# gsm_based_message_display_on_lcd.net
KiCad netlist of a schematic drawn in EAGLE
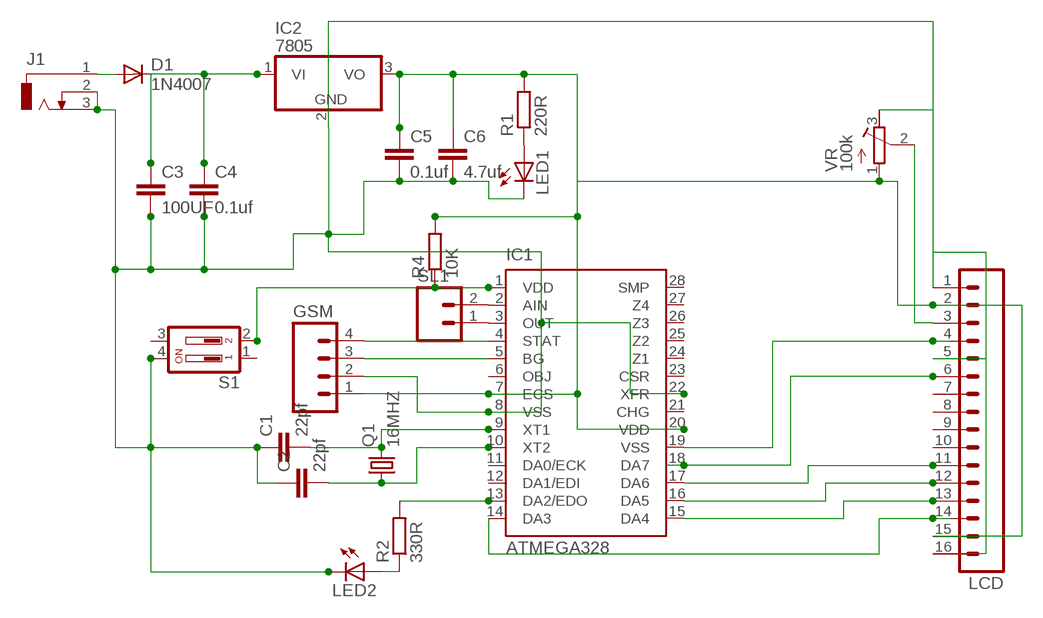
[diagram p0: schematic, sheet 1]

(export (version "E")
  (design (tool "Eeschema 10.0.6"))
  (components
    (comp (ref "C1")
      (value "22pf")
      (footprint "eagle-import:C2.5-2")
      (libsource (lib "eagle-import") (part "C2.5/2"))
    )
    (comp (ref "C2")
      (value "22pf")
      (footprint "eagle-import:C2.5-2")
      (libsource (lib "eagle-import") (part "C2.5/2"))
    )
    (comp (ref "C3")
      (value "100UF")
      (footprint "eagle-import:C2.5-2")
      (libsource (lib "eagle-import") (part "C2.5/2"))
    )
    (comp (ref "C4")
      (value "0.1uf")
      (footprint "eagle-import:C2.5-2")
      (libsource (lib "eagle-import") (part "C2.5/2"))
    )
    (comp (ref "C5")
      (value "0.1uf")
      (footprint "eagle-import:C2.5-2")
      (libsource (lib "eagle-import") (part "C2.5/2"))
    )
    (comp (ref "C6")
      (value "4.7uf")
      (footprint "eagle-import:C2.5-2")
      (libsource (lib "eagle-import") (part "C2.5/2"))
    )
    (comp (ref "D1")
      (value "1N4007")
      (footprint "eagle-import:DO41-10")
      (libsource (lib "eagle-import") (part "1N4004"))
    )
    (comp (ref "GSM")
      (value "M04")
      (footprint "eagle-import:04P")
      (libsource (lib "eagle-import") (part "M04"))
    )
    (comp (ref "IC1")
      (value "ATMEGA328")
      (footprint "eagle-import:DIL28-3")
      (libsource (lib "eagle-import") (part "QT9701BD"))
    )
    (comp (ref "IC2")
      (value "7805")
      (footprint "eagle-import:TO220V")
      (libsource (lib "eagle-import") (part "78TV6"))
    )
    (comp (ref "J1")
      (value "DCJ0303")
      (footprint "eagle-import:DCJ0303")
      (libsource (lib "eagle-import") (part "DCJ0303"))
    )
    (comp (ref "LCD")
      (value "M16")
      (footprint "eagle-import:16P")
      (libsource (lib "eagle-import") (part "M16"))
    )
    (comp (ref "LED1")
      (value "LED3MM")
      (footprint "eagle-import:LED3MM")
      (libsource (lib "eagle-import") (part "LED3MM"))
    )
    (comp (ref "LED2")
      (value "LED3MM")
      (footprint "eagle-import:LED3MM")
      (libsource (lib "eagle-import") (part "LED3MM"))
    )
    (comp (ref "Q1")
      (value "16MHZ")
      (footprint "eagle-import:HC49_S")
      (libsource (lib "eagle-import") (part "CRYSTALHC49S"))
    )
    (comp (ref "R1")
      (value "220R")
      (footprint "eagle-import:0207_10")
      (libsource (lib "eagle-import") (part "R-EU_0207/10"))
    )
    (comp (ref "R2")
      (value "330R")
      (footprint "eagle-import:0207_10")
      (libsource (lib "eagle-import") (part "R-EU_0207/10"))
    )
    (comp (ref "R4")
      (value "10K")
      (footprint "eagle-import:0207_10")
      (libsource (lib "eagle-import") (part "R-EU_0207/10"))
    )
    (comp (ref "S1")
      (value "DP02")
      (footprint "eagle-import:DP-02")
      (fields (field (name "MPN") "MCDP02"))
      (libsource (lib "eagle-import") (part "DP02"))
    )
    (comp (ref "SL1")
      (value "M02")
      (footprint "eagle-import:02P")
      (libsource (lib "eagle-import") (part "M02"))
    )
    (comp (ref "VR")
      (value "100k")
      (footprint "eagle-import:RTRIM64P")
      (libsource (lib "eagle-import") (part "R-TRIMM64P"))
    )
  )
  (nets
    (net (code "1") (name "Net-(D1-PadA)") (class "Default")
      (node (ref "D1") (pin "A") (pinfunction "A_A") (pintype "passive"))
      (node (ref "J1") (pin "1") (pinfunction "1_1") (pintype "passive"))
    )
    (net (code "2") (name "Net-(IC1-AIN)") (class "Default")
      (node (ref "IC1") (pin "2") (pinfunction "AIN_2") (pintype "input"))
      (node (ref "SL1") (pin "2") (pinfunction "2_2") (pintype "passive"))
    )
    (net (code "3") (name "Net-(IC1-BG)") (class "Default")
      (node (ref "GSM") (pin "3") (pinfunction "3_3") (pintype "passive"))
      (node (ref "IC1") (pin "5") (pinfunction "BG_5") (pintype "input"))
    )
    (net (code "4") (name "Net-(IC1-DA2{slash}EDO)") (class "Default")
      (node (ref "IC1") (pin "13") (pinfunction "DA2/EDO_13") (pintype "output"))
      (node (ref "R2") (pin "2") (pinfunction "2_2") (pintype "passive"))
    )
    (net (code "5") (name "Net-(IC1-DA3)") (class "Default")
      (node (ref "IC1") (pin "14") (pinfunction "DA3_14") (pintype "output"))
      (node (ref "LCD") (pin "14") (pinfunction "14_14") (pintype "passive"))
    )
    (net (code "6") (name "Net-(IC1-DA4)") (class "Default")
      (node (ref "IC1") (pin "15") (pinfunction "DA4_15") (pintype "output"))
      (node (ref "LCD") (pin "13") (pinfunction "13_13") (pintype "passive"))
    )
    (net (code "7") (name "Net-(IC1-DA5)") (class "Default")
      (node (ref "IC1") (pin "16") (pinfunction "DA5_16") (pintype "output"))
      (node (ref "LCD") (pin "12") (pinfunction "12_12") (pintype "passive"))
    )
    (net (code "8") (name "Net-(IC1-DA6)") (class "Default")
      (node (ref "IC1") (pin "17") (pinfunction "DA6_17") (pintype "output"))
      (node (ref "LCD") (pin "11") (pinfunction "11_11") (pintype "passive"))
    )
    (net (code "9") (name "Net-(IC1-DA7)") (class "Default")
      (node (ref "IC1") (pin "18") (pinfunction "DA7_18") (pintype "output"))
      (node (ref "LCD") (pin "6") (pinfunction "6_6") (pintype "passive"))
    )
    (net (code "10") (name "Net-(IC1-ECS)") (class "Default")
      (node (ref "C5") (pin "1") (pinfunction "1_1") (pintype "passive"))
      (node (ref "C6") (pin "1") (pinfunction "1_1") (pintype "passive"))
      (node (ref "GSM") (pin "1") (pinfunction "1_1") (pintype "passive"))
      (node (ref "IC1") (pin "20") (pinfunction "VDD_20") (pintype "input"))
      (node (ref "IC1") (pin "7") (pinfunction "ECS_7") (pintype "output"))
      (node (ref "IC2") (pin "3") (pinfunction "VO_3") (pintype "passive"))
      (node (ref "LCD") (pin "15") (pinfunction "15_15") (pintype "passive"))
      (node (ref "LCD") (pin "2") (pinfunction "2_2") (pintype "passive"))
      (node (ref "R1") (pin "2") (pinfunction "2_2") (pintype "passive"))
      (node (ref "R4") (pin "2") (pinfunction "2_2") (pintype "passive"))
      (node (ref "VR") (pin "1") (pinfunction "E_1") (pintype "passive"))
    )
    (net (code "11") (name "Net-(IC1-OUT)") (class "Default")
      (node (ref "IC1") (pin "3") (pinfunction "OUT_3") (pintype "output"))
      (node (ref "SL1") (pin "1") (pinfunction "1_1") (pintype "passive"))
    )
    (net (code "12") (name "Net-(IC1-STAT)") (class "Default")
      (node (ref "GSM") (pin "4") (pinfunction "4_4") (pintype "passive"))
      (node (ref "IC1") (pin "4") (pinfunction "STAT_4") (pintype "output"))
    )
    (net (code "13") (name "Net-(IC1-VDD-Pad1)") (class "Default")
      (node (ref "IC1") (pin "1") (pinfunction "VDD_1") (pintype "input"))
      (node (ref "R4") (pin "1") (pinfunction "1_1") (pintype "passive"))
      (node (ref "S1") (pin "2") (pinfunction "2_2") (pintype "passive"))
    )
    (net (code "14") (name "Net-(IC1-VSS-Pad19)") (class "Default")
      (node (ref "IC1") (pin "19") (pinfunction "VSS_19") (pintype "input"))
      (node (ref "LCD") (pin "4") (pinfunction "4_4") (pintype "passive"))
    )
    (net (code "15") (name "Net-(IC1-XFR)") (class "Default")
      (node (ref "C1") (pin "1") (pinfunction "1_1") (pintype "passive"))
      (node (ref "C2") (pin "1") (pinfunction "1_1") (pintype "passive"))
      (node (ref "C3") (pin "2") (pinfunction "2_2") (pintype "passive"))
      (node (ref "C4") (pin "2") (pinfunction "2_2") (pintype "passive"))
      (node (ref "C5") (pin "2") (pinfunction "2_2") (pintype "passive"))
      (node (ref "C6") (pin "2") (pinfunction "2_2") (pintype "passive"))
      (node (ref "GSM") (pin "2") (pinfunction "2_2") (pintype "passive"))
      (node (ref "IC1") (pin "22") (pinfunction "XFR_22") (pintype "output"))
      (node (ref "IC1") (pin "8") (pinfunction "VSS_8") (pintype "input"))
      (node (ref "IC2") (pin "2") (pinfunction "GND_2") (pintype "passive"))
      (node (ref "J1") (pin "2") (pinfunction "2_2") (pintype "passive"))
      (node (ref "J1") (pin "3") (pinfunction "3_3") (pintype "passive"))
      (node (ref "LCD") (pin "1") (pinfunction "1_1") (pintype "passive"))
      (node (ref "LCD") (pin "16") (pinfunction "16_16") (pintype "passive"))
      (node (ref "LCD") (pin "5") (pinfunction "5_5") (pintype "passive"))
      (node (ref "LED1") (pin "K") (pinfunction "C_K") (pintype "passive"))
      (node (ref "LED2") (pin "K") (pinfunction "C_K") (pintype "passive"))
      (node (ref "S1") (pin "4") (pinfunction "4_4") (pintype "passive"))
      (node (ref "VR") (pin "3") (pinfunction "A_3") (pintype "passive"))
    )
    (net (code "16") (name "Net-(IC1-XT1)") (class "Default")
      (node (ref "C1") (pin "2") (pinfunction "2_2") (pintype "passive"))
      (node (ref "IC1") (pin "9") (pinfunction "XT1_9") (pintype "input"))
      (node (ref "Q1") (pin "2") (pinfunction "2_2") (pintype "passive"))
    )
    (net (code "17") (name "Net-(IC1-XT2)") (class "Default")
      (node (ref "C2") (pin "2") (pinfunction "2_2") (pintype "passive"))
      (node (ref "IC1") (pin "10") (pinfunction "XT2_10") (pintype "output"))
      (node (ref "Q1") (pin "1") (pinfunction "1_1") (pintype "passive"))
    )
    (net (code "18") (name "Net-(IC2-VI)") (class "Default")
      (node (ref "C3") (pin "1") (pinfunction "1_1") (pintype "passive"))
      (node (ref "C4") (pin "1") (pinfunction "1_1") (pintype "passive"))
      (node (ref "D1") (pin "C") (pinfunction "C_C") (pintype "passive"))
      (node (ref "IC2") (pin "1") (pinfunction "VI_1") (pintype "input"))
    )
    (net (code "19") (name "Net-(LED1-PadA)") (class "Default")
      (node (ref "LED1") (pin "A") (pinfunction "A_A") (pintype "passive"))
      (node (ref "R1") (pin "1") (pinfunction "1_1") (pintype "passive"))
    )
    (net (code "20") (name "Net-(LED2-PadA)") (class "Default")
      (node (ref "LED2") (pin "A") (pinfunction "A_A") (pintype "passive"))
      (node (ref "R2") (pin "1") (pinfunction "1_1") (pintype "passive"))
    )
    (net (code "21") (name "Net-(VR-S)") (class "Default")
      (node (ref "LCD") (pin "3") (pinfunction "3_3") (pintype "passive"))
      (node (ref "VR") (pin "2") (pinfunction "S_2") (pintype "passive"))
    )
    (net (code "22") (name "unconnected-(IC1-CHG-Pad21)") (class "Default")
      (node (ref "IC1") (pin "21") (pinfunction "CHG_21") (pintype "output"))
    )
    (net (code "23") (name "unconnected-(IC1-CSR-Pad23)") (class "Default")
      (node (ref "IC1") (pin "23") (pinfunction "CSR_23") (pintype "output"))
    )
    (net (code "24") (name "unconnected-(IC1-DA0{slash}ECK-Pad11)") (class "Default")
      (node (ref "IC1") (pin "11") (pinfunction "DA0/ECK_11") (pintype "output"))
    )
    (net (code "25") (name "unconnected-(IC1-DA1{slash}EDI-Pad12)") (class "Default")
      (node (ref "IC1") (pin "12") (pinfunction "DA1/EDI_12") (pintype "output"))
    )
    (net (code "26") (name "unconnected-(IC1-OBJ-Pad6)") (class "Default")
      (node (ref "IC1") (pin "6") (pinfunction "OBJ_6") (pintype "input"))
    )
    (net (code "27") (name "unconnected-(IC1-SMP-Pad28)") (class "Default")
      (node (ref "IC1") (pin "28") (pinfunction "SMP_28") (pintype "output"))
    )
    (net (code "28") (name "unconnected-(IC1-Z1-Pad24)") (class "Default")
      (node (ref "IC1") (pin "24") (pinfunction "Z1_24") (pintype "output"))
    )
    (net (code "29") (name "unconnected-(IC1-Z2-Pad25)") (class "Default")
      (node (ref "IC1") (pin "25") (pinfunction "Z2_25") (pintype "output"))
    )
    (net (code "30") (name "unconnected-(IC1-Z3-Pad26)") (class "Default")
      (node (ref "IC1") (pin "26") (pinfunction "Z3_26") (pintype "output"))
    )
    (net (code "31") (name "unconnected-(IC1-Z4-Pad27)") (class "Default")
      (node (ref "IC1") (pin "27") (pinfunction "Z4_27") (pintype "output"))
    )
    (net (code "32") (name "unconnected-(LCD-Pad7)") (class "Default")
      (node (ref "LCD") (pin "7") (pinfunction "7_7") (pintype "passive"))
    )
    (net (code "33") (name "unconnected-(LCD-Pad8)") (class "Default")
      (node (ref "LCD") (pin "8") (pinfunction "8_8") (pintype "passive"))
    )
    (net (code "34") (name "unconnected-(LCD-Pad9)") (class "Default")
      (node (ref "LCD") (pin "9") (pinfunction "9_9") (pintype "passive"))
    )
    (net (code "35") (name "unconnected-(LCD-Pad10)") (class "Default")
      (node (ref "LCD") (pin "10") (pinfunction "10_10") (pintype "passive"))
    )
    (net (code "36") (name "unconnected-(S1-Pad1)") (class "Default")
      (node (ref "S1") (pin "1") (pinfunction "1_1") (pintype "passive"))
    )
    (net (code "37") (name "unconnected-(S1-Pad3)") (class "Default")
      (node (ref "S1") (pin "3") (pinfunction "3_3") (pintype "passive"))
    )
  )
)
